# QuadcopterRobocet.net
KiCad netlist of a schematic drawn in EAGLE
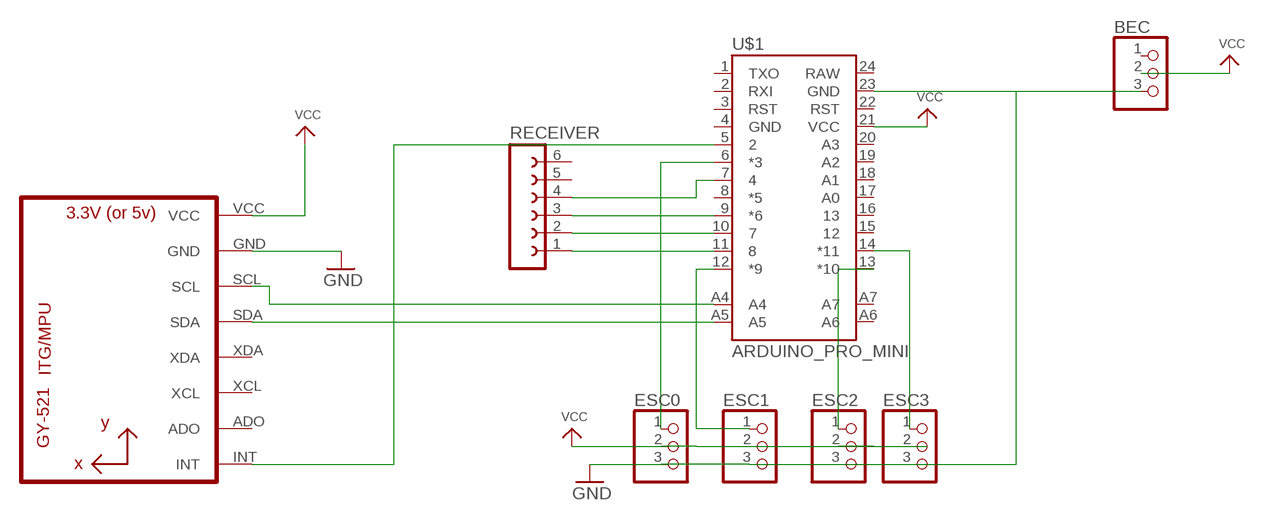
[diagram p0: schematic, sheet 1]

(export (version "E")
  (design (tool "Eeschema 10.0.6"))
  (components
    (comp (ref "BEC")
      (value "PINHD-1X3")
      (footprint "eagle-import:1X03")
      (libsource (lib "eagle-import") (part "PINHD-1X3"))
    )
    (comp (ref "ESC0")
      (value "PINHD-1X3")
      (footprint "eagle-import:1X03")
      (libsource (lib "eagle-import") (part "PINHD-1X3"))
    )
    (comp (ref "ESC1")
      (value "PINHD-1X3")
      (footprint "eagle-import:1X03")
      (libsource (lib "eagle-import") (part "PINHD-1X3"))
    )
    (comp (ref "ESC2")
      (value "PINHD-1X3")
      (footprint "eagle-import:1X03")
      (libsource (lib "eagle-import") (part "PINHD-1X3"))
    )
    (comp (ref "ESC3")
      (value "PINHD-1X3")
      (footprint "eagle-import:1X03")
      (libsource (lib "eagle-import") (part "PINHD-1X3"))
    )
    (comp (ref "RECEIVER")
      (value "FE06-1")
      (footprint "eagle-import:FE06")
      (libsource (lib "eagle-import") (part "FE06-1"))
    )
    (comp (ref "U$1")
      (value "ARDUINO_PRO_MINI")
      (footprint "eagle-import:ARDUINO_PRO_MINI")
      (libsource (lib "eagle-import") (part "ARDUINO_PRO_MINI"))
    )
    (comp (ref "U1")
      (value "GY-521MPU6050")
      (footprint "eagle-import:GY-521")
      (libsource (lib "eagle-import") (part "GY-521MPU6050"))
    )
  )
  (nets
    (net (code "1") (name "GND") (class "Default")
      (node (ref "BEC") (pin "3") (pinfunction "3_3") (pintype "passive"))
      (node (ref "ESC0") (pin "3") (pinfunction "3_3") (pintype "passive"))
      (node (ref "ESC1") (pin "3") (pinfunction "3_3") (pintype "passive"))
      (node (ref "ESC2") (pin "3") (pinfunction "3_3") (pintype "passive"))
      (node (ref "ESC3") (pin "3") (pinfunction "3_3") (pintype "passive"))
      (node (ref "U$1") (pin "23") (pinfunction "GND_23") (pintype "bidirectional"))
      (node (ref "U1") (pin "GND") (pinfunction "GND_GND") (pintype "bidirectional"))
    )
    (net (code "2") (name "Net-(U$1-*3)") (class "Default")
      (node (ref "ESC0") (pin "1") (pinfunction "1_1") (pintype "passive"))
      (node (ref "U$1") (pin "6") (pinfunction "*3_6") (pintype "bidirectional"))
    )
    (net (code "3") (name "Net-(U$1-*6)") (class "Default")
      (node (ref "RECEIVER") (pin "3") (pinfunction "3_3") (pintype "passive"))
      (node (ref "U$1") (pin "9") (pinfunction "*6_9") (pintype "bidirectional"))
    )
    (net (code "4") (name "Net-(U$1-*9)") (class "Default")
      (node (ref "ESC1") (pin "1") (pinfunction "1_1") (pintype "passive"))
      (node (ref "U$1") (pin "12") (pinfunction "*9_12") (pintype "bidirectional"))
    )
    (net (code "5") (name "Net-(U$1-*10)") (class "Default")
      (node (ref "ESC2") (pin "1") (pinfunction "1_1") (pintype "passive"))
      (node (ref "U$1") (pin "13") (pinfunction "*10_13") (pintype "bidirectional"))
    )
    (net (code "6") (name "Net-(U$1-*11)") (class "Default")
      (node (ref "ESC3") (pin "1") (pinfunction "1_1") (pintype "passive"))
      (node (ref "U$1") (pin "14") (pinfunction "*11_14") (pintype "bidirectional"))
    )
    (net (code "7") (name "Net-(U$1-2)") (class "Default")
      (node (ref "U$1") (pin "5") (pinfunction "2_5") (pintype "bidirectional"))
      (node (ref "U1") (pin "INT") (pinfunction "INT_INT") (pintype "bidirectional"))
    )
    (net (code "8") (name "Net-(U$1-4)") (class "Default")
      (node (ref "RECEIVER") (pin "4") (pinfunction "4_4") (pintype "passive"))
      (node (ref "U$1") (pin "7") (pinfunction "4_7") (pintype "bidirectional"))
    )
    (net (code "9") (name "Net-(U$1-7)") (class "Default")
      (node (ref "RECEIVER") (pin "2") (pinfunction "2_2") (pintype "passive"))
      (node (ref "U$1") (pin "10") (pinfunction "7_10") (pintype "bidirectional"))
    )
    (net (code "10") (name "Net-(U$1-8)") (class "Default")
      (node (ref "RECEIVER") (pin "1") (pinfunction "1_1") (pintype "passive"))
      (node (ref "U$1") (pin "11") (pinfunction "8_11") (pintype "bidirectional"))
    )
    (net (code "11") (name "Net-(U$1-PadA4)") (class "Default")
      (node (ref "U$1") (pin "A4") (pinfunction "A4_A4") (pintype "bidirectional"))
      (node (ref "U1") (pin "SCL") (pinfunction "SCL_SCL") (pintype "bidirectional"))
    )
    (net (code "12") (name "Net-(U$1-PadA5)") (class "Default")
      (node (ref "U$1") (pin "A5") (pinfunction "A5_A5") (pintype "bidirectional"))
      (node (ref "U1") (pin "SDA") (pinfunction "SDA_SDA") (pintype "bidirectional"))
    )
    (net (code "13") (name "VCC") (class "Default")
      (node (ref "BEC") (pin "2") (pinfunction "2_2") (pintype "passive"))
      (node (ref "ESC0") (pin "2") (pinfunction "2_2") (pintype "passive"))
      (node (ref "ESC1") (pin "2") (pinfunction "2_2") (pintype "passive"))
      (node (ref "ESC2") (pin "2") (pinfunction "2_2") (pintype "passive"))
      (node (ref "ESC3") (pin "2") (pinfunction "2_2") (pintype "passive"))
      (node (ref "U$1") (pin "21") (pinfunction "VCC_21") (pintype "bidirectional"))
      (node (ref "U1") (pin "VCC") (pinfunction "VCC_VCC") (pintype "bidirectional"))
    )
    (net (code "14") (name "unconnected-(BEC-Pad1)") (class "Default")
      (node (ref "BEC") (pin "1") (pinfunction "1_1") (pintype "passive"))
    )
    (net (code "15") (name "unconnected-(RECEIVER-Pad5)") (class "Default")
      (node (ref "RECEIVER") (pin "5") (pinfunction "5_5") (pintype "passive"))
    )
    (net (code "16") (name "unconnected-(RECEIVER-Pad6)") (class "Default")
      (node (ref "RECEIVER") (pin "6") (pinfunction "6_6") (pintype "passive"))
    )
    (net (code "17") (name "unconnected-(U$1-*5-Pad8)") (class "Default")
      (node (ref "U$1") (pin "8") (pinfunction "*5_8") (pintype "bidirectional"))
    )
    (net (code "18") (name "unconnected-(U$1-12-Pad15)") (class "Default")
      (node (ref "U$1") (pin "15") (pinfunction "12_15") (pintype "bidirectional"))
    )
    (net (code "19") (name "unconnected-(U$1-13-Pad16)") (class "Default")
      (node (ref "U$1") (pin "16") (pinfunction "13_16") (pintype "bidirectional"))
    )
    (net (code "20") (name "unconnected-(U$1-A0-Pad17)") (class "Default")
      (node (ref "U$1") (pin "17") (pinfunction "A0_17") (pintype "bidirectional"))
    )
    (net (code "21") (name "unconnected-(U$1-A1-Pad18)") (class "Default")
      (node (ref "U$1") (pin "18") (pinfunction "A1_18") (pintype "bidirectional"))
    )
    (net (code "22") (name "unconnected-(U$1-A2-Pad19)") (class "Default")
      (node (ref "U$1") (pin "19") (pinfunction "A2_19") (pintype "bidirectional"))
    )
    (net (code "23") (name "unconnected-(U$1-A3-Pad20)") (class "Default")
      (node (ref "U$1") (pin "20") (pinfunction "A3_20") (pintype "bidirectional"))
    )
    (net (code "24") (name "unconnected-(U$1-GND-Pad4)") (class "Default")
      (node (ref "U$1") (pin "4") (pinfunction "GND_4") (pintype "bidirectional"))
    )
    (net (code "25") (name "unconnected-(U$1-PadA6)") (class "Default")
      (node (ref "U$1") (pin "A6") (pinfunction "A6_A6") (pintype "bidirectional"))
    )
    (net (code "26") (name "unconnected-(U$1-PadA7)") (class "Default")
      (node (ref "U$1") (pin "A7") (pinfunction "A7_A7") (pintype "bidirectional"))
    )
    (net (code "27") (name "unconnected-(U$1-RAW-Pad24)") (class "Default")
      (node (ref "U$1") (pin "24") (pinfunction "RAW_24") (pintype "bidirectional"))
    )
    (net (code "28") (name "unconnected-(U$1-RST-Pad3)") (class "Default")
      (node (ref "U$1") (pin "3") (pinfunction "RST_3") (pintype "bidirectional"))
    )
    (net (code "29") (name "unconnected-(U$1-RST-Pad22)") (class "Default")
      (node (ref "U$1") (pin "22") (pinfunction "RST_22") (pintype "bidirectional"))
    )
    (net (code "30") (name "unconnected-(U$1-RXI-Pad2)") (class "Default")
      (node (ref "U$1") (pin "2") (pinfunction "RXI_2") (pintype "bidirectional"))
    )
    (net (code "31") (name "unconnected-(U$1-TXO-Pad1)") (class "Default")
      (node (ref "U$1") (pin "1") (pinfunction "TXO_1") (pintype "bidirectional"))
    )
    (net (code "32") (name "unconnected-(U1-PadADO)") (class "Default")
      (node (ref "U1") (pin "ADO") (pinfunction "ADO_ADO") (pintype "bidirectional"))
    )
    (net (code "33") (name "unconnected-(U1-PadXCL)") (class "Default")
      (node (ref "U1") (pin "XCL") (pinfunction "XCL_XCL") (pintype "bidirectional"))
    )
    (net (code "34") (name "unconnected-(U1-PadXDA)") (class "Default")
      (node (ref "U1") (pin "XDA") (pinfunction "XDA_XDA") (pintype "bidirectional"))
    )
  )
)
